# Esquematico.net
KiCad netlist of a schematic drawn in Altium Designer
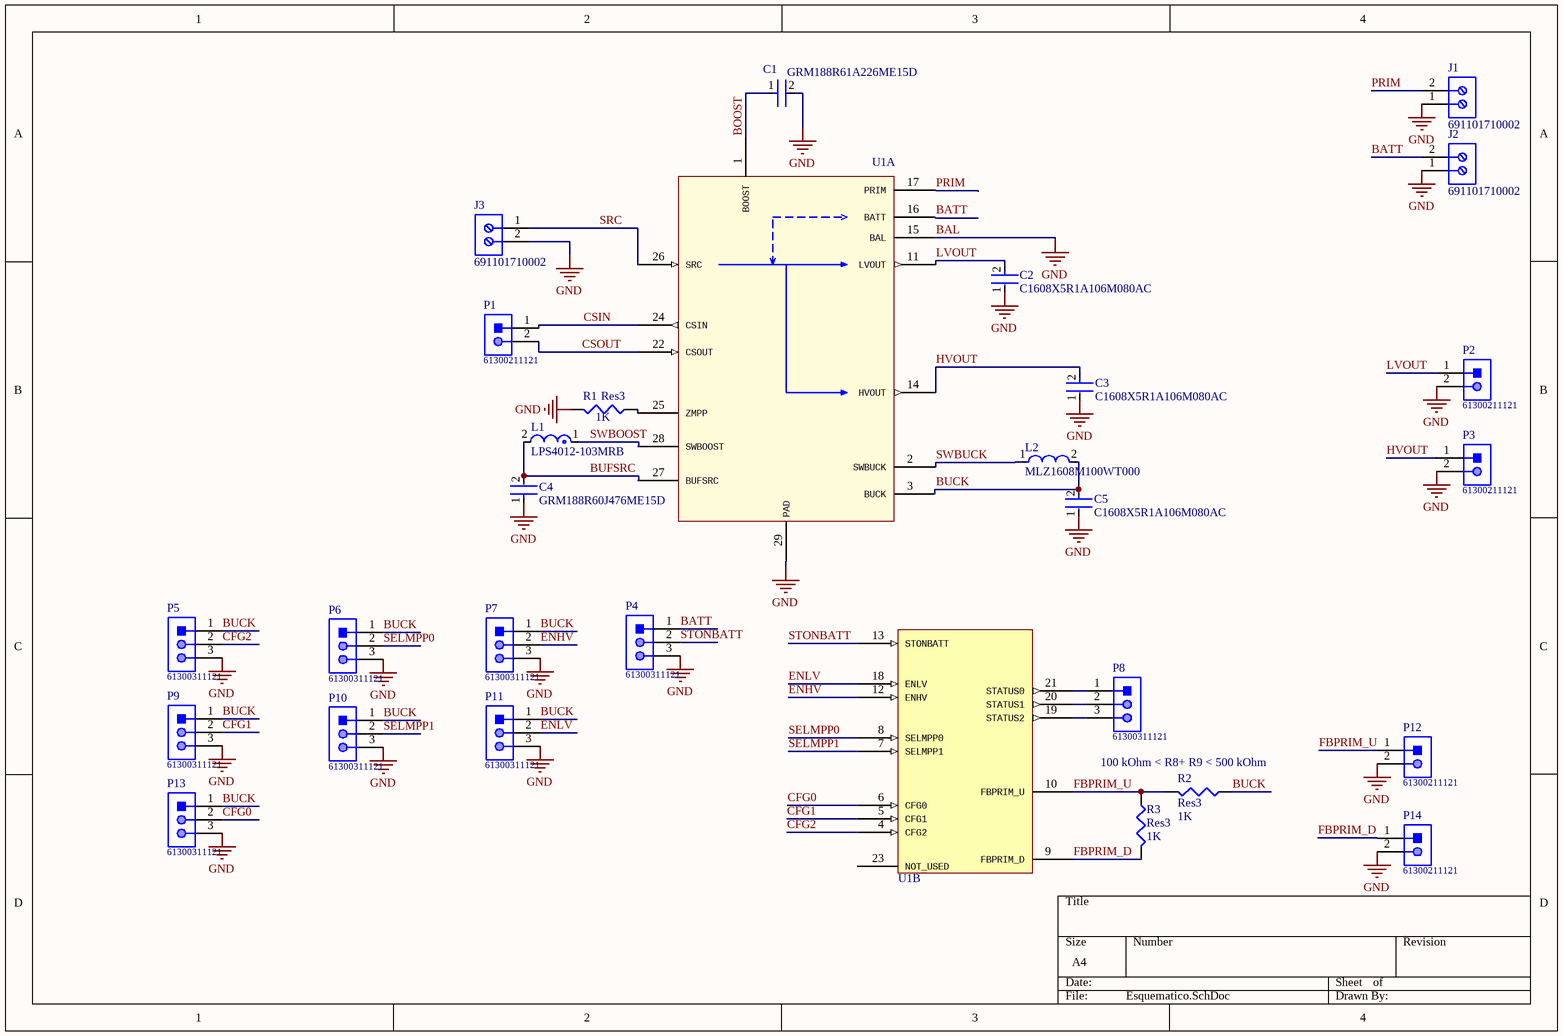
[diagram p0: Esquematico.SchDoc]

(export (version "E")
  (design (tool "Eeschema 10.0.6"))
  (components
    (comp (ref "C1")
      (value "GRM188R61A226ME15D")
      (footprint "FP-GRM188-0_2-IPC_C")
      (description "Chip Multilayer Ceramic Capacitors for General Purpose, 0603, 22uF, X5R, 15%, 20%, 10V")
      (fields (field (name "TOLERANCE") "20%"))
      (libsource (lib "Altium Content Vault") (part "11868f565c42a9108669ba33697ecf6"))
    )
    (comp (ref "C2")
      (value "C1608X5R1A106M080AC")
      (footprint "FP-C1608-080-0_1-IPC_A")
      (description "Multilayer Ceramic Capacitors 10μF ±20% 10V X5R SMD 0603")
      (fields (field (name "TOLERANCE") "20%"))
      (libsource (lib "Altium Content Vault") (part "236180d848d6139a670b325ea6854c9"))
    )
    (comp (ref "C3")
      (value "C1608X5R1A106M080AC")
      (footprint "FP-C1608-080-0_1-IPC_A")
      (description "Multilayer Ceramic Capacitors 10μF ±20% 10V X5R SMD 0603")
      (fields (field (name "TOLERANCE") "20%"))
      (libsource (lib "Altium Content Vault") (part "236180d848d6139a670b325ea6854c9"))
    )
    (comp (ref "C4")
      (value "GRM188R60J476ME15D")
      (footprint "FP-GRM188-0_2-IPC_B")
      (description "Chip Multilayer Ceramic Capacitors for General Purpose, 0603, 47uF, X5R, 15%, 20%, 6.3V")
      (fields (field (name "TOLERANCE") "20%"))
      (libsource (lib "Altium Content Vault") (part "11868f565c42a9108669ba33697ecf6"))
    )
    (comp (ref "C5")
      (value "C1608X5R1A106M080AC")
      (footprint "FP-C1608-080-0_1-IPC_A")
      (description "Multilayer Ceramic Capacitors 10μF ±20% 10V X5R SMD 0603")
      (fields (field (name "TOLERANCE") "20%"))
      (libsource (lib "Altium Content Vault") (part "236180d848d6139a670b325ea6854c9"))
    )
    (comp (ref "J1")
      (value "691101710002")
      (footprint "691101710002")
      (description "Series 101 - 5.00 mm Horizontal Entry Modular with Pressure Clamp WR-TBL, 2 pin")
      (fields (field (name "MANUFACTURER") "Wurth Elektronik") (field (name "PUBLISHER") "WurthElektronik"))
      (libsource (lib "Altium Content Vault") (part "WE-CN-1P-F-TB2"))
    )
    (comp (ref "J2")
      (value "691101710002")
      (footprint "691101710002")
      (description "Series 101 - 5.00 mm Horizontal Entry Modular with Pressure Clamp WR-TBL, 2 pin")
      (fields (field (name "MANUFACTURER") "Wurth Elektronik") (field (name "PUBLISHER") "WurthElektronik"))
      (libsource (lib "") (part "WE-CN-1P-F-TB2_1"))
    )
    (comp (ref "J3")
      (value "691101710002")
      (footprint "691101710002")
      (description "Series 101 - 5.00 mm Horizontal Entry Modular with Pressure Clamp WR-TBL, 2 pin")
      (fields (field (name "MANUFACTURER") "Wurth Elektronik") (field (name "PUBLISHER") "WurthElektronik"))
      (libsource (lib "Altium Content Vault") (part "WE-CN-1P-F-TB2"))
    )
    (comp (ref "L1")
      (value "LPS4012-103MRB")
      (footprint "FP-LPS4012-MFG")
      (description "Power Inductor (SMD), 10 µH, 550 mA, Shielded, 1 A, LPS4012 Series, 3.9mm x 3.9mm x 1.1mm")
      (fields (field (name "TOLERANCE") "20%"))
      (libsource (lib "Altium Content Vault") (part "4cc4b267dca4c8e51f7102f422741d8"))
    )
    (comp (ref "L2")
      (value "MLZ1608M100WT000")
      (footprint "FP-MLZ1608-IPC_C")
      (description "Shielded Multilayer Inductor 10uH ±20% 250mA 1365mΩ SMD 0603")
      (fields (field (name "TOLERANCE") "20%"))
      (libsource (lib "Altium Content Vault") (part "725321dda6339637d4d059423bc1c3c"))
    )
    (comp (ref "P1")
      (value "61300211121")
      (footprint "61300211121")
      (description "THT Vertical Pin Header WR-PHD, Pitch 2.54 mm, Single Row, 2 pins")
      (fields (field (name "MANUFACTURER") "Wurth Elektronik") (field (name "PUBLISHER") "WurthElektronik"))
      (libsource (lib "") (part "WE-CN-1P-M-R2_1"))
    )
    (comp (ref "P2")
      (value "61300211121")
      (footprint "61300211121")
      (description "THT Vertical Pin Header WR-PHD, Pitch 2.54 mm, Single Row, 2 pins")
      (fields (field (name "MANUFACTURER") "Wurth Elektronik") (field (name "PUBLISHER") "WurthElektronik"))
      (libsource (lib "Altium Content Vault") (part "WE-CN-1P-M-R2"))
    )
    (comp (ref "P3")
      (value "61300211121")
      (footprint "61300211121")
      (description "THT Vertical Pin Header WR-PHD, Pitch 2.54 mm, Single Row, 2 pins")
      (fields (field (name "MANUFACTURER") "Wurth Elektronik") (field (name "PUBLISHER") "WurthElektronik"))
      (libsource (lib "Altium Content Vault") (part "WE-CN-1P-M-R2"))
    )
    (comp (ref "P4")
      (value "61300311121")
      (footprint "61300311121")
      (description "THT Vertical Pin Header WR-PHD, Pitch 2.54 mm, Single Row, 3 pins")
      (fields (field (name "MANUFACTURER") "Wurth Elektronik") (field (name "PUBLISHER") "WurthElektronik"))
      (libsource (lib "Altium Content Vault") (part "WE-CN-1P-M-R3"))
    )
    (comp (ref "P5")
      (value "61300311121")
      (footprint "61300311121")
      (description "THT Vertical Pin Header WR-PHD, Pitch 2.54 mm, Single Row, 3 pins")
      (fields (field (name "MANUFACTURER") "Wurth Elektronik") (field (name "PUBLISHER") "WurthElektronik"))
      (libsource (lib "Altium Content Vault") (part "WE-CN-1P-M-R3"))
    )
    (comp (ref "P6")
      (value "61300311121")
      (footprint "61300311121")
      (description "THT Vertical Pin Header WR-PHD, Pitch 2.54 mm, Single Row, 3 pins")
      (fields (field (name "MANUFACTURER") "Wurth Elektronik") (field (name "PUBLISHER") "WurthElektronik"))
      (libsource (lib "Altium Content Vault") (part "WE-CN-1P-M-R3"))
    )
    (comp (ref "P7")
      (value "61300311121")
      (footprint "61300311121")
      (description "THT Vertical Pin Header WR-PHD, Pitch 2.54 mm, Single Row, 3 pins")
      (fields (field (name "MANUFACTURER") "Wurth Elektronik") (field (name "PUBLISHER") "WurthElektronik"))
      (libsource (lib "Altium Content Vault") (part "WE-CN-1P-M-R3"))
    )
    (comp (ref "P8")
      (value "61300311121")
      (footprint "61300311121")
      (description "THT Vertical Pin Header WR-PHD, Pitch 2.54 mm, Single Row, 3 pins")
      (fields (field (name "MANUFACTURER") "Wurth Elektronik") (field (name "PUBLISHER") "WurthElektronik"))
      (libsource (lib "") (part "WE-CN-1P-M-R3_1"))
    )
    (comp (ref "P9")
      (value "61300311121")
      (footprint "61300311121")
      (description "THT Vertical Pin Header WR-PHD, Pitch 2.54 mm, Single Row, 3 pins")
      (fields (field (name "MANUFACTURER") "Wurth Elektronik") (field (name "PUBLISHER") "WurthElektronik"))
      (libsource (lib "Altium Content Vault") (part "WE-CN-1P-M-R3"))
    )
    (comp (ref "P10")
      (value "61300311121")
      (footprint "61300311121")
      (description "THT Vertical Pin Header WR-PHD, Pitch 2.54 mm, Single Row, 3 pins")
      (fields (field (name "MANUFACTURER") "Wurth Elektronik") (field (name "PUBLISHER") "WurthElektronik"))
      (libsource (lib "Altium Content Vault") (part "WE-CN-1P-M-R3"))
    )
    (comp (ref "P11")
      (value "61300311121")
      (footprint "61300311121")
      (description "THT Vertical Pin Header WR-PHD, Pitch 2.54 mm, Single Row, 3 pins")
      (fields (field (name "MANUFACTURER") "Wurth Elektronik") (field (name "PUBLISHER") "WurthElektronik"))
      (libsource (lib "Altium Content Vault") (part "WE-CN-1P-M-R3"))
    )
    (comp (ref "P12")
      (value "61300211121")
      (footprint "61300211121")
      (description "THT Vertical Pin Header WR-PHD, Pitch 2.54 mm, Single Row, 2 pins")
      (fields (field (name "MANUFACTURER") "Wurth Elektronik") (field (name "PUBLISHER") "WurthElektronik"))
      (libsource (lib "Altium Content Vault") (part "WE-CN-1P-M-R2"))
    )
    (comp (ref "P13")
      (value "61300311121")
      (footprint "61300311121")
      (description "THT Vertical Pin Header WR-PHD, Pitch 2.54 mm, Single Row, 3 pins")
      (fields (field (name "MANUFACTURER") "Wurth Elektronik") (field (name "PUBLISHER") "WurthElektronik"))
      (libsource (lib "Altium Content Vault") (part "WE-CN-1P-M-R3"))
    )
    (comp (ref "P14")
      (value "61300211121")
      (footprint "61300211121")
      (description "THT Vertical Pin Header WR-PHD, Pitch 2.54 mm, Single Row, 2 pins")
      (fields (field (name "MANUFACTURER") "Wurth Elektronik") (field (name "PUBLISHER") "WurthElektronik"))
      (libsource (lib "Altium Content Vault") (part "WE-CN-1P-M-R2"))
    )
    (comp (ref "R1")
      (value "Res3")
      (footprint "J1-0603")
      (description "Resistor")
      (fields (field (name "ALTIUM_VALUE") "1K") (field (name "PUBLISHER") "Altium Limited"))
      (libsource (lib "Miscellaneous Devices") (part "Res3"))
    )
    (comp (ref "R2")
      (value "Res3")
      (footprint "J1-0603")
      (description "Resistor")
      (fields (field (name "ALTIUM_VALUE") "1K") (field (name "PUBLISHER") "Altium Limited"))
      (libsource (lib "Miscellaneous Devices") (part "Res3"))
    )
    (comp (ref "R3")
      (value "Res3")
      (footprint "J1-0603")
      (description "Resistor")
      (fields (field (name "ALTIUM_VALUE") "1K") (field (name "PUBLISHER") "Altium Limited"))
      (libsource (lib "Miscellaneous Devices") (part "Res3"))
    )
    (comp (ref "U1")
      (value "AEM20940 - Symbol QFN28")
      (footprint "QFN28 5x5mm Pitch=0.5mm ThPad=3.15x3.15mm")
      (libsource (lib "AEM20940") (part "AEM20940 - Symbol QFN28"))
    )
  )
  (nets
    (net (code "1") (name "/BATT") (class "Default")
      (node (ref "J2") (pin "2") (pinfunction "2_2") (pintype "passive"))
      (node (ref "P4") (pin "1") (pinfunction "1_1") (pintype "passive"))
      (node (ref "U1") (pin "16") (pinfunction "BATT_16") (pintype "passive"))
    )
    (net (code "2") (name "/BOOST") (class "Default")
      (node (ref "C1") (pin "1") (pinfunction "1_1") (pintype "passive"))
      (node (ref "U1") (pin "1") (pinfunction "BOOST_1") (pintype "passive"))
    )
    (net (code "3") (name "/BUCK") (class "Default")
      (node (ref "C5") (pin "2") (pinfunction "2_2") (pintype "passive"))
      (node (ref "L2") (pin "2") (pinfunction "2_2") (pintype "passive"))
      (node (ref "P10") (pin "1") (pinfunction "1_1") (pintype "passive"))
      (node (ref "P11") (pin "1") (pinfunction "1_1") (pintype "passive"))
      (node (ref "P13") (pin "1") (pinfunction "1_1") (pintype "passive"))
      (node (ref "P5") (pin "1") (pinfunction "1_1") (pintype "passive"))
      (node (ref "P6") (pin "1") (pinfunction "1_1") (pintype "passive"))
      (node (ref "P7") (pin "1") (pinfunction "1_1") (pintype "passive"))
      (node (ref "P9") (pin "1") (pinfunction "1_1") (pintype "passive"))
      (node (ref "R2") (pin "1") (pinfunction "1_1") (pintype "passive"))
      (node (ref "U1") (pin "3") (pinfunction "BUCK_3") (pintype "passive"))
    )
    (net (code "4") (name "/BUFSRC") (class "Default")
      (node (ref "C4") (pin "2") (pinfunction "2_2") (pintype "passive"))
      (node (ref "L1") (pin "2") (pinfunction "2_2") (pintype "passive"))
      (node (ref "U1") (pin "27") (pinfunction "BUFSRC_27") (pintype "passive"))
    )
    (net (code "5") (name "/CFG0") (class "Default")
      (node (ref "P13") (pin "2") (pinfunction "2_2") (pintype "passive"))
      (node (ref "U1") (pin "6") (pinfunction "CFG0_6") (pintype "input"))
    )
    (net (code "6") (name "/CFG1") (class "Default")
      (node (ref "P9") (pin "2") (pinfunction "2_2") (pintype "passive"))
      (node (ref "U1") (pin "5") (pinfunction "CFG1_5") (pintype "input"))
    )
    (net (code "7") (name "/CFG2") (class "Default")
      (node (ref "P5") (pin "2") (pinfunction "2_2") (pintype "passive"))
      (node (ref "U1") (pin "4") (pinfunction "CFG2_4") (pintype "input"))
    )
    (net (code "8") (name "/CSIN") (class "Default")
      (node (ref "P1") (pin "1") (pinfunction "1_1") (pintype "passive"))
      (node (ref "U1") (pin "24") (pinfunction "CSIN_24") (pintype "output"))
    )
    (net (code "9") (name "/CSOUT") (class "Default")
      (node (ref "P1") (pin "2") (pinfunction "2_2") (pintype "passive"))
      (node (ref "U1") (pin "22") (pinfunction "CSOUT_22") (pintype "input"))
    )
    (net (code "10") (name "/ENHV") (class "Default")
      (node (ref "P7") (pin "2") (pinfunction "2_2") (pintype "passive"))
      (node (ref "U1") (pin "12") (pinfunction "ENHV_12") (pintype "input"))
    )
    (net (code "11") (name "/ENLV") (class "Default")
      (node (ref "P11") (pin "2") (pinfunction "2_2") (pintype "passive"))
      (node (ref "U1") (pin "18") (pinfunction "ENLV_18") (pintype "input"))
    )
    (net (code "12") (name "/FBPRIM_D") (class "Default")
      (node (ref "P14") (pin "1") (pinfunction "1_1") (pintype "passive"))
      (node (ref "R3") (pin "2") (pinfunction "2_2") (pintype "passive"))
      (node (ref "U1") (pin "9") (pinfunction "FBPRIM_D_9") (pintype "passive"))
    )
    (net (code "13") (name "/FBPRIM_U") (class "Default")
      (node (ref "P12") (pin "1") (pinfunction "1_1") (pintype "passive"))
      (node (ref "R2") (pin "2") (pinfunction "2_2") (pintype "passive"))
      (node (ref "R3") (pin "1") (pinfunction "1_1") (pintype "passive"))
      (node (ref "U1") (pin "10") (pinfunction "FBPRIM_U_10") (pintype "passive"))
    )
    (net (code "14") (name "/HVOUT") (class "Default")
      (node (ref "C3") (pin "2") (pinfunction "2_2") (pintype "passive"))
      (node (ref "P3") (pin "1") (pinfunction "1_1") (pintype "passive"))
      (node (ref "U1") (pin "14") (pinfunction "HVOUT_14") (pintype "output"))
    )
    (net (code "15") (name "/LVOUT") (class "Default")
      (node (ref "C2") (pin "2") (pinfunction "2_2") (pintype "passive"))
      (node (ref "P2") (pin "1") (pinfunction "1_1") (pintype "passive"))
      (node (ref "U1") (pin "11") (pinfunction "LVOUT_11") (pintype "output"))
    )
    (net (code "16") (name "/PRIM") (class "Default")
      (node (ref "J1") (pin "2") (pinfunction "2_2") (pintype "passive"))
      (node (ref "U1") (pin "17") (pinfunction "PRIM_17") (pintype "passive"))
    )
    (net (code "17") (name "/SELMPP0") (class "Default")
      (node (ref "P6") (pin "2") (pinfunction "2_2") (pintype "passive"))
      (node (ref "U1") (pin "8") (pinfunction "SELMPP0_8") (pintype "input"))
    )
    (net (code "18") (name "/SELMPP1") (class "Default")
      (node (ref "P10") (pin "2") (pinfunction "2_2") (pintype "passive"))
      (node (ref "U1") (pin "7") (pinfunction "SELMPP1_7") (pintype "input"))
    )
    (net (code "19") (name "/SRC") (class "Default")
      (node (ref "J3") (pin "1") (pinfunction "1_1") (pintype "passive"))
      (node (ref "U1") (pin "26") (pinfunction "SRC_26") (pintype "input"))
    )
    (net (code "20") (name "/STONBATT") (class "Default")
      (node (ref "P4") (pin "2") (pinfunction "2_2") (pintype "passive"))
      (node (ref "U1") (pin "13") (pinfunction "STONBATT_13") (pintype "input"))
    )
    (net (code "21") (name "/SWBOOST") (class "Default")
      (node (ref "L1") (pin "1") (pinfunction "1_1") (pintype "passive"))
      (node (ref "U1") (pin "28") (pinfunction "SWBOOST_28") (pintype "passive"))
    )
    (net (code "22") (name "/SWBUCK") (class "Default")
      (node (ref "L2") (pin "1") (pinfunction "1_1") (pintype "passive"))
      (node (ref "U1") (pin "2") (pinfunction "SWBUCK_2") (pintype "passive"))
    )
    (net (code "23") (name "GND") (class "Default")
      (node (ref "C1") (pin "2") (pinfunction "2_2") (pintype "passive"))
      (node (ref "C2") (pin "1") (pinfunction "1_1") (pintype "passive"))
      (node (ref "C3") (pin "1") (pinfunction "1_1") (pintype "passive"))
      (node (ref "C4") (pin "1") (pinfunction "1_1") (pintype "passive"))
      (node (ref "C5") (pin "1") (pinfunction "1_1") (pintype "passive"))
      (node (ref "J1") (pin "1") (pinfunction "1_1") (pintype "passive"))
      (node (ref "J2") (pin "1") (pinfunction "1_1") (pintype "passive"))
      (node (ref "J3") (pin "2") (pinfunction "2_2") (pintype "passive"))
      (node (ref "P10") (pin "3") (pinfunction "3_3") (pintype "passive"))
      (node (ref "P11") (pin "3") (pinfunction "3_3") (pintype "passive"))
      (node (ref "P12") (pin "2") (pinfunction "2_2") (pintype "passive"))
      (node (ref "P13") (pin "3") (pinfunction "3_3") (pintype "passive"))
      (node (ref "P14") (pin "2") (pinfunction "2_2") (pintype "passive"))
      (node (ref "P2") (pin "2") (pinfunction "2_2") (pintype "passive"))
      (node (ref "P3") (pin "2") (pinfunction "2_2") (pintype "passive"))
      (node (ref "P4") (pin "3") (pinfunction "3_3") (pintype "passive"))
      (node (ref "P5") (pin "3") (pinfunction "3_3") (pintype "passive"))
      (node (ref "P6") (pin "3") (pinfunction "3_3") (pintype "passive"))
      (node (ref "P7") (pin "3") (pinfunction "3_3") (pintype "passive"))
      (node (ref "P9") (pin "3") (pinfunction "3_3") (pintype "passive"))
      (node (ref "R1") (pin "2") (pinfunction "2_2") (pintype "passive"))
      (node (ref "U1") (pin "15") (pinfunction "BAL_15") (pintype "passive"))
      (node (ref "U1") (pin "29") (pinfunction "PAD_29") (pintype "power_in"))
    )
    (net (code "24") (name "Net-(U1A-ZMPP)") (class "Default")
      (node (ref "R1") (pin "1") (pinfunction "1_1") (pintype "passive"))
      (node (ref "U1") (pin "25") (pinfunction "ZMPP_25") (pintype "passive"))
    )
    (net (code "25") (name "Net-(U1B-STATUS0)") (class "Default")
      (node (ref "P8") (pin "1") (pinfunction "1_1") (pintype "passive"))
      (node (ref "U1") (pin "21") (pinfunction "STATUS0_21") (pintype "output"))
    )
    (net (code "26") (name "Net-(U1B-STATUS1)") (class "Default")
      (node (ref "P8") (pin "2") (pinfunction "2_2") (pintype "passive"))
      (node (ref "U1") (pin "20") (pinfunction "STATUS1_20") (pintype "output"))
    )
    (net (code "27") (name "Net-(U1B-STATUS2)") (class "Default")
      (node (ref "P8") (pin "3") (pinfunction "3_3") (pintype "passive"))
      (node (ref "U1") (pin "19") (pinfunction "STATUS2_19") (pintype "output"))
    )
    (net (code "28") (name "unconnected-(U1B-NOT_USED-Pad23)") (class "Default")
      (node (ref "U1") (pin "23") (pinfunction "NOT_USED_23") (pintype "passive"))
    )
  )
)
